# FourierHT.net
KiCad netlist of a schematic drawn in Altium Designer
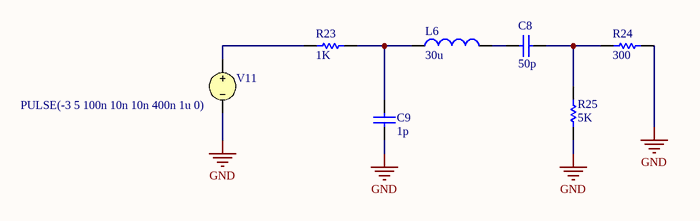
[diagram p0: FourierHT.SchDoc]

(export (version "E")
  (design (tool "Eeschema 10.0.6"))
  (components
    (comp (ref "C8")
      (value "50p")
      (description "Capacitor")
      (libsource (lib "Simulation Generic Components") (part "Capacitor"))
    )
    (comp (ref "C9")
      (value "1p")
      (description "Capacitor")
      (libsource (lib "Simulation Generic Components") (part "Capacitor"))
    )
    (comp (ref "L6")
      (value "30u")
      (description "Inductor")
      (libsource (lib "Simulation Generic Components") (part "Inductor"))
    )
    (comp (ref "R23")
      (value "1K")
      (description "Resistor")
      (libsource (lib "Simulation Generic Components") (part "Resistor"))
    )
    (comp (ref "R24")
      (value "300")
      (description "Resistor")
      (libsource (lib "Simulation Generic Components") (part "Resistor"))
    )
    (comp (ref "R25")
      (value "5K")
      (description "Resistor")
      (libsource (lib "Simulation Generic Components") (part "Resistor"))
    )
    (comp (ref "V11")
      (value "PULSE(-3 5 100n 10n 10n 400n 1u 0)")
      (description "Voltage Source")
      (fields (field (name "PUBLISHER") "Altium Limited"))
      (libsource (lib "Simulation Generic Components") (part "VSRC"))
    )
  )
  (nets
    (net (code "1") (name "GND") (class "Default")
      (node (ref "C9") (pin "1") (pinfunction "1_1") (pintype "passive"))
      (node (ref "R24") (pin "2") (pinfunction "2_2") (pintype "passive"))
      (node (ref "R25") (pin "1") (pinfunction "1_1") (pintype "passive"))
      (node (ref "V11") (pin "2") (pinfunction "2_2") (pintype "passive"))
    )
    (net (code "2") (name "Net-(C8-Pad1)") (class "Default")
      (node (ref "C8") (pin "1") (pinfunction "1_1") (pintype "passive"))
      (node (ref "R24") (pin "1") (pinfunction "1_1") (pintype "passive"))
      (node (ref "R25") (pin "2") (pinfunction "2_2") (pintype "passive"))
    )
    (net (code "3") (name "Net-(C8-Pad2)") (class "Default")
      (node (ref "C8") (pin "2") (pinfunction "2_2") (pintype "passive"))
      (node (ref "L6") (pin "2") (pinfunction "2_2") (pintype "passive"))
    )
    (net (code "4") (name "Net-(C9-Pad2)") (class "Default")
      (node (ref "C9") (pin "2") (pinfunction "2_2") (pintype "passive"))
      (node (ref "L6") (pin "1") (pinfunction "1_1") (pintype "passive"))
      (node (ref "R23") (pin "2") (pinfunction "2_2") (pintype "passive"))
    )
    (net (code "5") (name "Net-(R23-Pad1)") (class "Default")
      (node (ref "R23") (pin "1") (pinfunction "1_1") (pintype "passive"))
      (node (ref "V11") (pin "1") (pinfunction "1_1") (pintype "passive"))
    )
  )
)
